# Sheet1.net
KiCad netlist of a schematic drawn in Altium Designer
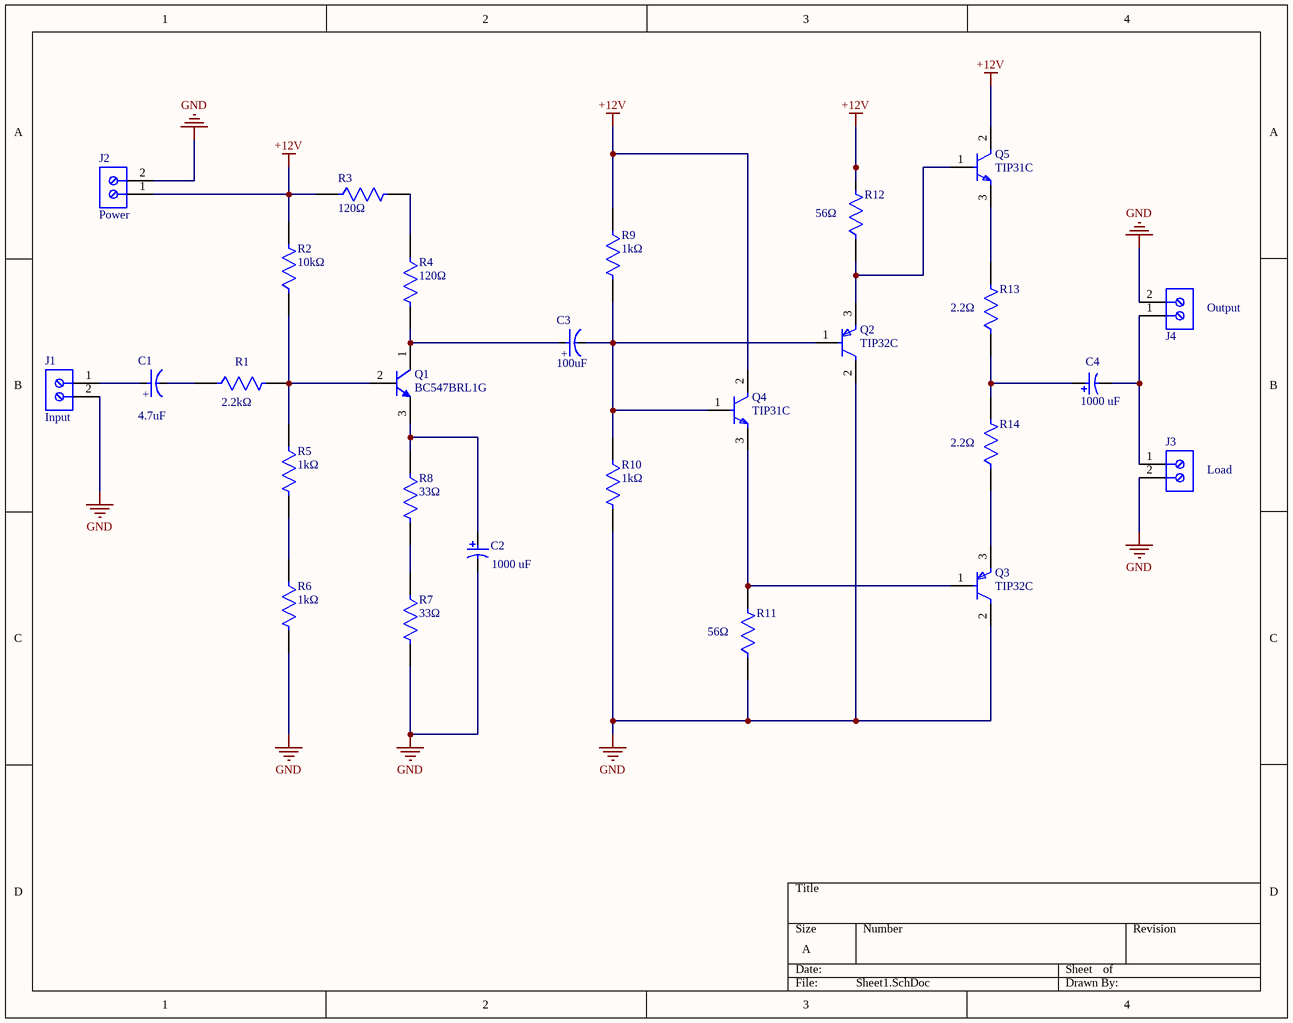
[diagram p0: Sheet1.SchDoc]

(export (version "E")
  (design (tool "Eeschema 10.0.6"))
  (components
    (comp (ref "C1")
      (value "EEUFM1H220_small")
      (footprint "FP-RAD-TH-D_5_0_5-L_11_1-MFG")
      (description "Aluminum Electrolytic Capacitors (Radial Lead Type) 22uF ±20% 50V")
      (fields
        (field (name "TOLERANCE") "20%")
        (field (name "VOLTAGE") "50V")
        (field (name "CAPACITANCE") "4.7uF")
      )
      (libsource (lib "Altium Content Vault") (part "a00bbbee19879c290e62620ae7e47b1"))
    )
    (comp (ref "C2")
      (value "PLF1A471MDO1_big")
      (footprint "NIC-PLF-10x13-2_V")
      (description "Aluminum Electrolytic Capacitor, 470 uF +/-20%, 10 V, -55 to 105 degC, 2-Pin THD, RoHS")
      (fields
        (field (name "RATED CAPACITANCE") "1000 uF")
        (field (name "MANUFACTURER") "Nichicon")
        (field (name "PARTNUMBER") "PLF1A471MDO1")
      )
      (libsource (lib "Altium Content Vault") (part "NIC-CAP-P-2"))
    )
    (comp (ref "C3")
      (value "EEUFM1H220_small")
      (footprint "FP-RAD-TH-D_5_0_5-L_11_1-MFG")
      (description "Aluminum Electrolytic Capacitors (Radial Lead Type) 22uF ±20% 50V")
      (fields
        (field (name "TOLERANCE") "20%")
        (field (name "VOLTAGE") "50V")
        (field (name "CAPACITANCE") "100uF")
      )
      (libsource (lib "Altium Content Vault") (part "a00bbbee19879c290e62620ae7e47b1"))
    )
    (comp (ref "C4")
      (value "PLF1A471MDO1_big")
      (footprint "NIC-PLF-10x13-2_V")
      (description "Aluminum Electrolytic Capacitor, 470 uF +/-20%, 10 V, -55 to 105 degC, 2-Pin THD, RoHS")
      (fields
        (field (name "RATED CAPACITANCE") "1000 uF")
        (field (name "MANUFACTURER") "Nichicon")
        (field (name "PARTNUMBER") "PLF1A471MDO1")
      )
      (libsource (lib "Altium Content Vault") (part "NIC-CAP-P-2"))
    )
    (comp (ref "J1")
      (value "Input")
      (footprint "TECO-282836-2_V")
      (description "Female Header, Pitch 5 mm, 1 x 2 Position, Height 10 mm, Tail Length 3.5 mm, Rohs, Bulk")
      (fields (field (name "VOLTAGE") "300V") (field (name "MANUFACTURER") "TE Connectivity"))
      (libsource (lib "Altium Content Vault") (part "CN-1P-F-TB2"))
    )
    (comp (ref "J2")
      (value "Power")
      (footprint "TECO-282836-2_V")
      (description "Female Header, Pitch 5 mm, 1 x 2 Position, Height 10 mm, Tail Length 3.5 mm, Rohs, Bulk")
      (fields (field (name "VOLTAGE") "300V") (field (name "MANUFACTURER") "TE Connectivity"))
      (libsource (lib "Altium Content Vault") (part "CN-1P-F-TB2"))
    )
    (comp (ref "J3")
      (value "Load")
      (footprint "TECO-282836-2_V")
      (description "Female Header, Pitch 5 mm, 1 x 2 Position, Height 10 mm, Tail Length 3.5 mm, Rohs, Bulk")
      (fields (field (name "VOLTAGE") "300V") (field (name "MANUFACTURER") "TE Connectivity"))
      (libsource (lib "Altium Content Vault") (part "CN-1P-F-TB2"))
    )
    (comp (ref "J4")
      (value "Output")
      (footprint "TECO-282836-2_V")
      (description "Female Header, Pitch 5 mm, 1 x 2 Position, Height 10 mm, Tail Length 3.5 mm, Rohs, Bulk")
      (fields (field (name "VOLTAGE") "300V") (field (name "MANUFACTURER") "TE Connectivity"))
      (libsource (lib "Altium Content Vault") (part "CN-1P-F-TB2"))
    )
    (comp (ref "Q1")
      (value "BC547BRL1G")
      (footprint "ONSC-TO-92-3-29-11_AM_BL")
      (description "Amplifier Transistor, NPN Silicon, 3-Pin TO-92, Pb-Free, Tape and Reel")
      (fields (field (name "MANUFACTURER") "On Semiconductor"))
      (libsource (lib "Altium Content Vault") (part "ONSC-NPN-C1B2E3-3"))
    )
    (comp (ref "Q2")
      (value "TIP32C")
      (footprint "FP-TO-220-P0A0015988-MFG")
      (description "TRANS PNP 100V 3A TO-220")
      (fields
        (field (name "MANUFACTURER") "STMicroelectronics")
        (field (name "OCTOPART") "https://octopart.com/tip32c-stmicroelectronics-353617")
      )
      (libsource (lib "Altium Content Vault") (part "802a31d42ca070764d097f06bc9597f"))
    )
    (comp (ref "Q3")
      (value "TIP32C")
      (footprint "FP-TO-220-P0A0015988-MFG")
      (description "TRANS PNP 100V 3A TO-220")
      (fields
        (field (name "MANUFACTURER") "STMicroelectronics")
        (field (name "OCTOPART") "https://octopart.com/tip32c-stmicroelectronics-353617")
      )
      (libsource (lib "Altium Content Vault") (part "802a31d42ca070764d097f06bc9597f"))
    )
    (comp (ref "Q4")
      (value "TIP31C")
      (footprint "FP-TO-220-P0A0015988-MFG")
      (description "TRANS NPN 100V 3A TO-220")
      (fields
        (field (name "OCTOPART") "https://octopart.com/tip31c-stmicroelectronics-15555")
        (field (name "MANUFACTURER") "STMicroelectronics")
      )
      (libsource (lib "Altium Content Vault") (part "1c57d9dae74fe2702546667b0e849db"))
    )
    (comp (ref "Q5")
      (value "TIP31C")
      (footprint "FP-TO-220-P0A0015988-MFG")
      (description "TRANS NPN 100V 3A TO-220")
      (fields
        (field (name "OCTOPART") "https://octopart.com/tip31c-stmicroelectronics-15555")
        (field (name "MANUFACTURER") "STMicroelectronics")
      )
      (libsource (lib "Altium Content Vault") (part "1c57d9dae74fe2702546667b0e849db"))
    )
    (comp (ref "R1")
      (value "2.2kΩ")
      (footprint "FP-MFR-25-MFG")
      (description "RES 1.18K OHM 1/4W 1% AXIAL")
      (fields (field (name "MANUFACTURER") "Yageo") (field (name "TOLERANCE") "1%"))
      (libsource (lib "Altium Content Vault") (part "1029c3af85768c4190bb7ad29bc67b5"))
    )
    (comp (ref "R2")
      (value "10kΩ")
      (footprint "FP-MFR-25-MFG")
      (description "RES 1.18K OHM 1/4W 1% AXIAL")
      (fields (field (name "MANUFACTURER") "Yageo") (field (name "TOLERANCE") "1%"))
      (libsource (lib "Altium Content Vault") (part "1029c3af85768c4190bb7ad29bc67b5"))
    )
    (comp (ref "R3")
      (value "MFR-25FBF52-1K18")
      (footprint "FP-MFR-25-MFG")
      (description "RES 1.18K OHM 1/4W 1% AXIAL")
      (fields
        (field (name "MANUFACTURER") "Yageo")
        (field (name "TOLERANCE") "1%")
        (field (name "RESISTANCE") "120Ω")
      )
      (libsource (lib "Altium Content Vault") (part "1029c3af85768c4190bb7ad29bc67b5"))
    )
    (comp (ref "R4")
      (value "MFR-25FBF52-1K18")
      (footprint "FP-MFR-25-MFG")
      (description "RES 1.18K OHM 1/4W 1% AXIAL")
      (fields
        (field (name "MANUFACTURER") "Yageo")
        (field (name "TOLERANCE") "1%")
        (field (name "RESISTANCE") "120Ω")
      )
      (libsource (lib "Altium Content Vault") (part "1029c3af85768c4190bb7ad29bc67b5"))
    )
    (comp (ref "R5")
      (value "1kΩ")
      (footprint "FP-MFR-25-MFG")
      (description "RES 1.18K OHM 1/4W 1% AXIAL")
      (fields (field (name "MANUFACTURER") "Yageo") (field (name "TOLERANCE") "1%"))
      (libsource (lib "Altium Content Vault") (part "1029c3af85768c4190bb7ad29bc67b5"))
    )
    (comp (ref "R6")
      (value "1kΩ")
      (footprint "FP-MFR-25-MFG")
      (description "RES 1.18K OHM 1/4W 1% AXIAL")
      (fields (field (name "MANUFACTURER") "Yageo") (field (name "TOLERANCE") "1%"))
      (libsource (lib "Altium Content Vault") (part "1029c3af85768c4190bb7ad29bc67b5"))
    )
    (comp (ref "R7")
      (value "MFR-25FBF52-1K18")
      (footprint "FP-MFR-25-MFG")
      (description "RES 1.18K OHM 1/4W 1% AXIAL")
      (fields
        (field (name "MANUFACTURER") "Yageo")
        (field (name "TOLERANCE") "1%")
        (field (name "RESISTANCE") "33Ω")
      )
      (libsource (lib "Altium Content Vault") (part "1029c3af85768c4190bb7ad29bc67b5"))
    )
    (comp (ref "R8")
      (value "MFR-25FBF52-1K18")
      (footprint "FP-MFR-25-MFG")
      (description "RES 1.18K OHM 1/4W 1% AXIAL")
      (fields
        (field (name "MANUFACTURER") "Yageo")
        (field (name "TOLERANCE") "1%")
        (field (name "RESISTANCE") "33Ω")
      )
      (libsource (lib "Altium Content Vault") (part "1029c3af85768c4190bb7ad29bc67b5"))
    )
    (comp (ref "R9")
      (value "1kΩ")
      (footprint "FP-MFR-25-MFG")
      (description "RES 1.18K OHM 1/4W 1% AXIAL")
      (fields (field (name "MANUFACTURER") "Yageo") (field (name "TOLERANCE") "1%"))
      (libsource (lib "Altium Content Vault") (part "1029c3af85768c4190bb7ad29bc67b5"))
    )
    (comp (ref "R10")
      (value "1kΩ")
      (footprint "FP-MFR-25-MFG")
      (description "RES 1.18K OHM 1/4W 1% AXIAL")
      (fields (field (name "MANUFACTURER") "Yageo") (field (name "TOLERANCE") "1%"))
      (libsource (lib "Altium Content Vault") (part "1029c3af85768c4190bb7ad29bc67b5"))
    )
    (comp (ref "R11")
      (value "15FR010E")
      (footprint "FP-15FR010E-MFG")
      (description "RES 0.01 OHM 5W 1% AXIAL")
      (fields (field (name "RESISTANCE") "56Ω") (field (name "TOLERANCE") "1%"))
      (libsource (lib "Altium Content Vault") (part "1029c3af85768c4190bb7ad29bc67b5"))
    )
    (comp (ref "R12")
      (value "15FR010E")
      (footprint "FP-15FR010E-MFG")
      (description "RES 0.01 OHM 5W 1% AXIAL")
      (fields (field (name "RESISTANCE") "56Ω") (field (name "TOLERANCE") "1%"))
      (libsource (lib "Altium Content Vault") (part "1029c3af85768c4190bb7ad29bc67b5"))
    )
    (comp (ref "R13")
      (value "15FR010E")
      (footprint "FP-15FR010E-MFG")
      (description "RES 0.01 OHM 5W 1% AXIAL")
      (fields (field (name "RESISTANCE") "2.2Ω") (field (name "TOLERANCE") "1%"))
      (libsource (lib "Altium Content Vault") (part "1029c3af85768c4190bb7ad29bc67b5"))
    )
    (comp (ref "R14")
      (value "15FR010E")
      (footprint "FP-15FR010E-MFG")
      (description "RES 0.01 OHM 5W 1% AXIAL")
      (fields (field (name "RESISTANCE") "2.2Ω") (field (name "TOLERANCE") "1%"))
      (libsource (lib "Altium Content Vault") (part "1029c3af85768c4190bb7ad29bc67b5"))
    )
  )
  (nets
    (net (code "1") (name "+12V") (class "Default")
      (node (ref "J2") (pin "1") (pinfunction "1_1") (pintype "passive"))
      (node (ref "Q4") (pin "2") (pinfunction "C_2") (pintype "passive"))
      (node (ref "Q5") (pin "2") (pinfunction "C_2") (pintype "passive"))
      (node (ref "R12") (pin "2") (pinfunction "2_2") (pintype "passive"))
      (node (ref "R2") (pin "2") (pinfunction "2_2") (pintype "passive"))
      (node (ref "R3") (pin "1") (pinfunction "1_1") (pintype "passive"))
      (node (ref "R9") (pin "1") (pinfunction "1_1") (pintype "passive"))
    )
    (net (code "2") (name "GND") (class "Default")
      (node (ref "C2") (pin "2") (pinfunction "2_2") (pintype "passive"))
      (node (ref "J1") (pin "2") (pinfunction "2_2") (pintype "passive"))
      (node (ref "J2") (pin "2") (pinfunction "2_2") (pintype "passive"))
      (node (ref "J3") (pin "2") (pinfunction "2_2") (pintype "passive"))
      (node (ref "J4") (pin "2") (pinfunction "2_2") (pintype "passive"))
      (node (ref "Q2") (pin "2") (pinfunction "C_2") (pintype "passive"))
      (node (ref "Q3") (pin "2") (pinfunction "C_2") (pintype "passive"))
      (node (ref "R10") (pin "2") (pinfunction "2_2") (pintype "passive"))
      (node (ref "R11") (pin "1") (pinfunction "1_1") (pintype "passive"))
      (node (ref "R6") (pin "2") (pinfunction "2_2") (pintype "passive"))
      (node (ref "R7") (pin "2") (pinfunction "2_2") (pintype "passive"))
    )
    (net (code "3") (name "Net-(C1-A)") (class "Default")
      (node (ref "C1") (pin "2") (pinfunction "A_2") (pintype "passive"))
      (node (ref "J1") (pin "1") (pinfunction "1_1") (pintype "passive"))
    )
    (net (code "4") (name "Net-(C1-C)") (class "Default")
      (node (ref "C1") (pin "1") (pinfunction "C_1") (pintype "passive"))
      (node (ref "R1") (pin "1") (pinfunction "1_1") (pintype "passive"))
    )
    (net (code "5") (name "Net-(C3-A)") (class "Default")
      (node (ref "C3") (pin "2") (pinfunction "A_2") (pintype "passive"))
      (node (ref "Q1") (pin "1") (pinfunction "C_1") (pintype "passive"))
      (node (ref "R4") (pin "2") (pinfunction "2_2") (pintype "passive"))
    )
    (net (code "6") (name "Net-(C3-C)") (class "Default")
      (node (ref "C3") (pin "1") (pinfunction "C_1") (pintype "passive"))
      (node (ref "Q2") (pin "1") (pinfunction "B_1") (pintype "passive"))
      (node (ref "Q4") (pin "1") (pinfunction "B_1") (pintype "passive"))
      (node (ref "R10") (pin "1") (pinfunction "1_1") (pintype "passive"))
      (node (ref "R9") (pin "2") (pinfunction "2_2") (pintype "passive"))
    )
    (net (code "7") (name "Net-(C4-Pad1)") (class "Default")
      (node (ref "C4") (pin "1") (pinfunction "1_1") (pintype "passive"))
      (node (ref "R13") (pin "1") (pinfunction "1_1") (pintype "passive"))
      (node (ref "R14") (pin "2") (pinfunction "2_2") (pintype "passive"))
    )
    (net (code "8") (name "Net-(C4-Pad2)") (class "Default")
      (node (ref "C4") (pin "2") (pinfunction "2_2") (pintype "passive"))
      (node (ref "J3") (pin "1") (pinfunction "1_1") (pintype "passive"))
      (node (ref "J4") (pin "1") (pinfunction "1_1") (pintype "passive"))
    )
    (net (code "9") (name "Net-(Q1-B)") (class "Default")
      (node (ref "Q1") (pin "2") (pinfunction "B_2") (pintype "passive"))
      (node (ref "R1") (pin "2") (pinfunction "2_2") (pintype "passive"))
      (node (ref "R2") (pin "1") (pinfunction "1_1") (pintype "passive"))
      (node (ref "R5") (pin "1") (pinfunction "1_1") (pintype "passive"))
    )
    (net (code "10") (name "Net-(Q1-E)") (class "Default")
      (node (ref "C2") (pin "1") (pinfunction "1_1") (pintype "passive"))
      (node (ref "Q1") (pin "3") (pinfunction "E_3") (pintype "passive"))
      (node (ref "R8") (pin "1") (pinfunction "1_1") (pintype "passive"))
    )
    (net (code "11") (name "Net-(Q2-E)") (class "Default")
      (node (ref "Q2") (pin "3") (pinfunction "E_3") (pintype "passive"))
      (node (ref "Q5") (pin "1") (pinfunction "B_1") (pintype "passive"))
      (node (ref "R12") (pin "1") (pinfunction "1_1") (pintype "passive"))
    )
    (net (code "12") (name "Net-(Q3-B)") (class "Default")
      (node (ref "Q3") (pin "1") (pinfunction "B_1") (pintype "passive"))
      (node (ref "Q4") (pin "3") (pinfunction "E_3") (pintype "passive"))
      (node (ref "R11") (pin "2") (pinfunction "2_2") (pintype "passive"))
    )
    (net (code "13") (name "Net-(Q3-E)") (class "Default")
      (node (ref "Q3") (pin "3") (pinfunction "E_3") (pintype "passive"))
      (node (ref "R14") (pin "1") (pinfunction "1_1") (pintype "passive"))
    )
    (net (code "14") (name "Net-(Q5-E)") (class "Default")
      (node (ref "Q5") (pin "3") (pinfunction "E_3") (pintype "passive"))
      (node (ref "R13") (pin "2") (pinfunction "2_2") (pintype "passive"))
    )
    (net (code "15") (name "Net-(R3-Pad2)") (class "Default")
      (node (ref "R3") (pin "2") (pinfunction "2_2") (pintype "passive"))
      (node (ref "R4") (pin "1") (pinfunction "1_1") (pintype "passive"))
    )
    (net (code "16") (name "Net-(R5-Pad2)") (class "Default")
      (node (ref "R5") (pin "2") (pinfunction "2_2") (pintype "passive"))
      (node (ref "R6") (pin "1") (pinfunction "1_1") (pintype "passive"))
    )
    (net (code "17") (name "Net-(R7-Pad1)") (class "Default")
      (node (ref "R7") (pin "1") (pinfunction "1_1") (pintype "passive"))
      (node (ref "R8") (pin "2") (pinfunction "2_2") (pintype "passive"))
    )
  )
)
